# MicroMultimeter_MCU_Sch.net
KiCad netlist of a schematic drawn in Altium Designer
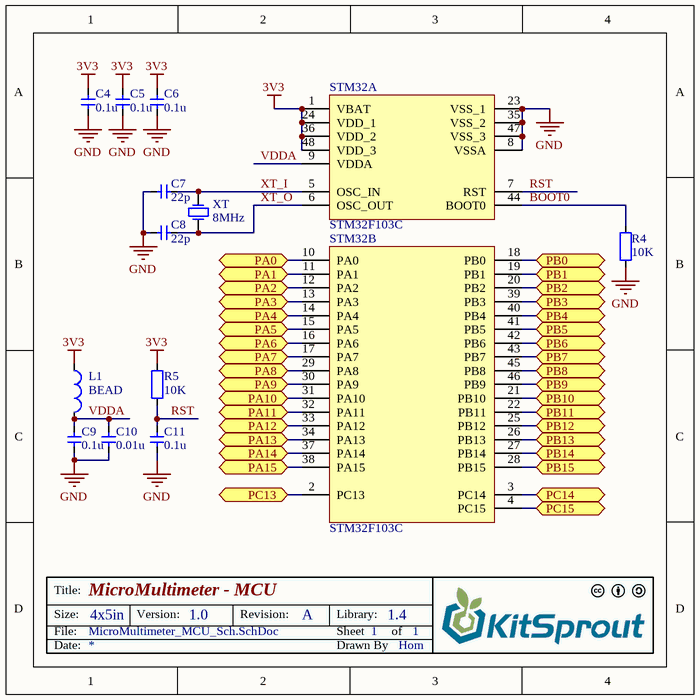
[diagram p0: MicroMultimeter_MCU_Sch.SchDoc]

(export (version "E")
  (design (tool "Eeschema 10.0.6"))
  (components
    (comp (ref "C4")
      (value "0.1u")
      (footprint "PCB_PassiveCap:CAP_0603")
      (description "Capacitor")
      (fields (field (name "Comment") "Cap_0603"))
      (libsource (lib "SCH_Passive") (part "Cap_0603"))
    )
    (comp (ref "C5")
      (value "0.1u")
      (footprint "PCB_PassiveCap:CAP_0603")
      (description "Capacitor")
      (fields (field (name "Comment") "Cap_0603"))
      (libsource (lib "SCH_Passive") (part "Cap_0603"))
    )
    (comp (ref "C6")
      (value "0.1u")
      (footprint "PCB_PassiveCap:CAP_0603")
      (description "Capacitor")
      (fields (field (name "Comment") "Cap_0603"))
      (libsource (lib "SCH_Passive") (part "Cap_0603"))
    )
    (comp (ref "C7")
      (value "22p")
      (footprint "PCB_PassiveCap:CAP_0603")
      (description "Capacitor")
      (fields (field (name "Comment") "Cap_0603"))
      (libsource (lib "SCH_Passive") (part "Cap_0603"))
    )
    (comp (ref "C8")
      (value "22p")
      (footprint "PCB_PassiveCap:CAP_0603")
      (description "Capacitor")
      (fields (field (name "Comment") "Cap_0603"))
      (libsource (lib "SCH_Passive") (part "Cap_0603"))
    )
    (comp (ref "C9")
      (value "0.1u")
      (footprint "PCB_PassiveCap:CAP_0603")
      (description "Capacitor")
      (fields (field (name "Comment") "Cap_0603"))
      (libsource (lib "SCH_Passive") (part "Cap_0603"))
    )
    (comp (ref "C10")
      (value "0.01u")
      (footprint "PCB_PassiveCap:CAP_0603")
      (description "Capacitor")
      (fields (field (name "Comment") "Cap_0603"))
      (libsource (lib "SCH_Passive") (part "Cap_0603"))
    )
    (comp (ref "C11")
      (value "0.1u")
      (footprint "PCB_PassiveCap:CAP_0603")
      (description "Capacitor")
      (fields (field (name "Comment") "Cap_0603"))
      (libsource (lib "SCH_Passive") (part "Cap_0603"))
    )
    (comp (ref "L1")
      (value "BEAD")
      (footprint "PCB_PassiveInd:IND_0603")
      (description "Inductor")
      (fields (field (name "Comment") "Ind_0603"))
      (libsource (lib "SCH_Passive") (part "Ind_0603"))
    )
    (comp (ref "R4")
      (value "10K")
      (footprint "PCB_PassiveRes:RES_0603")
      (description "Resistor")
      (fields (field (name "Comment") "Res_0603"))
      (libsource (lib "SCH_Passive") (part "Res_0603"))
    )
    (comp (ref "R5")
      (value "10K")
      (footprint "PCB_PassiveRes:RES_0603")
      (description "Resistor")
      (fields (field (name "Comment") "Res_0603"))
      (libsource (lib "SCH_Passive") (part "Res_0603"))
    )
    (comp (ref "STM32")
      (value "STM32F103C")
      (footprint "PCB_IntegratedCircuit:LQFP_P0.5_48")
      (description "MCU")
      (libsource (lib "SCH_IntegratedCircuit") (part "STM32F103C"))
    )
    (comp (ref "XT")
      (value "8MHz")
      (footprint "PCB_Oscillator:XT_5032_2")
      (description "Crystal Oscillator")
      (fields (field (name "Comment") "XTAL_5032_2P"))
      (libsource (lib "SCH_Oscillator") (part "XTAL_5032_2P"))
    )
  )
  (nets
    (net (code "1") (name "/BOOT0") (class "Default")
      (node (ref "R4") (pin "2") (pinfunction "2_2") (pintype "passive"))
      (node (ref "STM32") (pin "44") (pinfunction "BOOT0_44") (pintype "passive"))
    )
    (net (code "2") (name "/PA0") (class "Default")
      (node (ref "STM32") (pin "10") (pinfunction "PA0_10") (pintype "passive"))
    )
    (net (code "3") (name "/PA1") (class "Default")
      (node (ref "STM32") (pin "11") (pinfunction "PA1_11") (pintype "passive"))
    )
    (net (code "4") (name "/PA2") (class "Default")
      (node (ref "STM32") (pin "12") (pinfunction "PA2_12") (pintype "passive"))
    )
    (net (code "5") (name "/PA3") (class "Default")
      (node (ref "STM32") (pin "13") (pinfunction "PA3_13") (pintype "passive"))
    )
    (net (code "6") (name "/PA4") (class "Default")
      (node (ref "STM32") (pin "14") (pinfunction "PA4_14") (pintype "passive"))
    )
    (net (code "7") (name "/PA5") (class "Default")
      (node (ref "STM32") (pin "15") (pinfunction "PA5_15") (pintype "passive"))
    )
    (net (code "8") (name "/PA6") (class "Default")
      (node (ref "STM32") (pin "16") (pinfunction "PA6_16") (pintype "passive"))
    )
    (net (code "9") (name "/PA7") (class "Default")
      (node (ref "STM32") (pin "17") (pinfunction "PA7_17") (pintype "passive"))
    )
    (net (code "10") (name "/PA8") (class "Default")
      (node (ref "STM32") (pin "29") (pinfunction "PA8_29") (pintype "passive"))
    )
    (net (code "11") (name "/PA9") (class "Default")
      (node (ref "STM32") (pin "30") (pinfunction "PA9_30") (pintype "passive"))
    )
    (net (code "12") (name "/PA10") (class "Default")
      (node (ref "STM32") (pin "31") (pinfunction "PA10_31") (pintype "passive"))
    )
    (net (code "13") (name "/PA11") (class "Default")
      (node (ref "STM32") (pin "32") (pinfunction "PA11_32") (pintype "passive"))
    )
    (net (code "14") (name "/PA12") (class "Default")
      (node (ref "STM32") (pin "33") (pinfunction "PA12_33") (pintype "passive"))
    )
    (net (code "15") (name "/PA13") (class "Default")
      (node (ref "STM32") (pin "34") (pinfunction "PA13_34") (pintype "passive"))
    )
    (net (code "16") (name "/PA14") (class "Default")
      (node (ref "STM32") (pin "37") (pinfunction "PA14_37") (pintype "passive"))
    )
    (net (code "17") (name "/PA15") (class "Default")
      (node (ref "STM32") (pin "38") (pinfunction "PA15_38") (pintype "passive"))
    )
    (net (code "18") (name "/PB0") (class "Default")
      (node (ref "STM32") (pin "18") (pinfunction "PB0_18") (pintype "passive"))
    )
    (net (code "19") (name "/PB1") (class "Default")
      (node (ref "STM32") (pin "19") (pinfunction "PB1_19") (pintype "passive"))
    )
    (net (code "20") (name "/PB2") (class "Default")
      (node (ref "STM32") (pin "20") (pinfunction "PB2_20") (pintype "passive"))
    )
    (net (code "21") (name "/PB3") (class "Default")
      (node (ref "STM32") (pin "39") (pinfunction "PB3_39") (pintype "passive"))
    )
    (net (code "22") (name "/PB4") (class "Default")
      (node (ref "STM32") (pin "40") (pinfunction "PB4_40") (pintype "passive"))
    )
    (net (code "23") (name "/PB5") (class "Default")
      (node (ref "STM32") (pin "41") (pinfunction "PB5_41") (pintype "passive"))
    )
    (net (code "24") (name "/PB6") (class "Default")
      (node (ref "STM32") (pin "42") (pinfunction "PB6_42") (pintype "passive"))
    )
    (net (code "25") (name "/PB7") (class "Default")
      (node (ref "STM32") (pin "43") (pinfunction "PB7_43") (pintype "passive"))
    )
    (net (code "26") (name "/PB8") (class "Default")
      (node (ref "STM32") (pin "45") (pinfunction "PB8_45") (pintype "passive"))
    )
    (net (code "27") (name "/PB9") (class "Default")
      (node (ref "STM32") (pin "46") (pinfunction "PB9_46") (pintype "passive"))
    )
    (net (code "28") (name "/PB10") (class "Default")
      (node (ref "STM32") (pin "21") (pinfunction "PB10_21") (pintype "passive"))
    )
    (net (code "29") (name "/PB11") (class "Default")
      (node (ref "STM32") (pin "22") (pinfunction "PB11_22") (pintype "passive"))
    )
    (net (code "30") (name "/PB12") (class "Default")
      (node (ref "STM32") (pin "25") (pinfunction "PB12_25") (pintype "passive"))
    )
    (net (code "31") (name "/PB13") (class "Default")
      (node (ref "STM32") (pin "26") (pinfunction "PB13_26") (pintype "passive"))
    )
    (net (code "32") (name "/PB14") (class "Default")
      (node (ref "STM32") (pin "27") (pinfunction "PB14_27") (pintype "passive"))
    )
    (net (code "33") (name "/PB15") (class "Default")
      (node (ref "STM32") (pin "28") (pinfunction "PB15_28") (pintype "passive"))
    )
    (net (code "34") (name "/PC13") (class "Default")
      (node (ref "STM32") (pin "2") (pinfunction "PC13_2") (pintype "passive"))
    )
    (net (code "35") (name "/PC14") (class "Default")
      (node (ref "STM32") (pin "3") (pinfunction "PC14_3") (pintype "passive"))
    )
    (net (code "36") (name "/PC15") (class "Default")
      (node (ref "STM32") (pin "4") (pinfunction "PC15_4") (pintype "passive"))
    )
    (net (code "37") (name "/RST") (class "Default")
      (node (ref "C11") (pin "2") (pinfunction "2_2") (pintype "passive"))
      (node (ref "R5") (pin "1") (pinfunction "1_1") (pintype "passive"))
      (node (ref "STM32") (pin "7") (pinfunction "RST_7") (pintype "passive"))
    )
    (net (code "38") (name "/VDDA") (class "Default")
      (node (ref "C10") (pin "2") (pinfunction "2_2") (pintype "passive"))
      (node (ref "C9") (pin "2") (pinfunction "2_2") (pintype "passive"))
      (node (ref "L1") (pin "2") (pinfunction "2_2") (pintype "passive"))
      (node (ref "STM32") (pin "9") (pinfunction "VDDA_9") (pintype "passive"))
    )
    (net (code "39") (name "/XT_I") (class "Default")
      (node (ref "C7") (pin "1") (pinfunction "1_1") (pintype "passive"))
      (node (ref "STM32") (pin "5") (pinfunction "OSC_IN_5") (pintype "passive"))
      (node (ref "XT") (pin "2") (pinfunction "OSC2_2") (pintype "passive"))
    )
    (net (code "40") (name "/XT_O") (class "Default")
      (node (ref "C8") (pin "1") (pinfunction "1_1") (pintype "passive"))
      (node (ref "STM32") (pin "6") (pinfunction "OSC_OUT_6") (pintype "passive"))
      (node (ref "XT") (pin "1") (pinfunction "OSC1_1") (pintype "passive"))
    )
    (net (code "41") (name "3V3") (class "Default")
      (node (ref "C4") (pin "2") (pinfunction "2_2") (pintype "passive"))
      (node (ref "C5") (pin "2") (pinfunction "2_2") (pintype "passive"))
      (node (ref "C6") (pin "2") (pinfunction "2_2") (pintype "passive"))
      (node (ref "L1") (pin "1") (pinfunction "1_1") (pintype "passive"))
      (node (ref "R5") (pin "2") (pinfunction "2_2") (pintype "passive"))
      (node (ref "STM32") (pin "1") (pinfunction "VBAT_1") (pintype "passive"))
      (node (ref "STM32") (pin "24") (pinfunction "VDD_1_24") (pintype "passive"))
      (node (ref "STM32") (pin "36") (pinfunction "VDD_2_36") (pintype "passive"))
      (node (ref "STM32") (pin "48") (pinfunction "VDD_3_48") (pintype "passive"))
    )
    (net (code "42") (name "GND") (class "Default")
      (node (ref "C10") (pin "1") (pinfunction "1_1") (pintype "passive"))
      (node (ref "C11") (pin "1") (pinfunction "1_1") (pintype "passive"))
      (node (ref "C4") (pin "1") (pinfunction "1_1") (pintype "passive"))
      (node (ref "C5") (pin "1") (pinfunction "1_1") (pintype "passive"))
      (node (ref "C6") (pin "1") (pinfunction "1_1") (pintype "passive"))
      (node (ref "C7") (pin "2") (pinfunction "2_2") (pintype "passive"))
      (node (ref "C8") (pin "2") (pinfunction "2_2") (pintype "passive"))
      (node (ref "C9") (pin "1") (pinfunction "1_1") (pintype "passive"))
      (node (ref "R4") (pin "1") (pinfunction "1_1") (pintype "passive"))
      (node (ref "STM32") (pin "23") (pinfunction "VSS_1_23") (pintype "passive"))
      (node (ref "STM32") (pin "35") (pinfunction "VSS_2_35") (pintype "passive"))
      (node (ref "STM32") (pin "47") (pinfunction "VSS_3_47") (pintype "passive"))
      (node (ref "STM32") (pin "8") (pinfunction "VSSA_8") (pintype "passive"))
    )
  )
)
